# snow_depth_gauge_1D.net
KiCad netlist of a schematic drawn in EAGLE
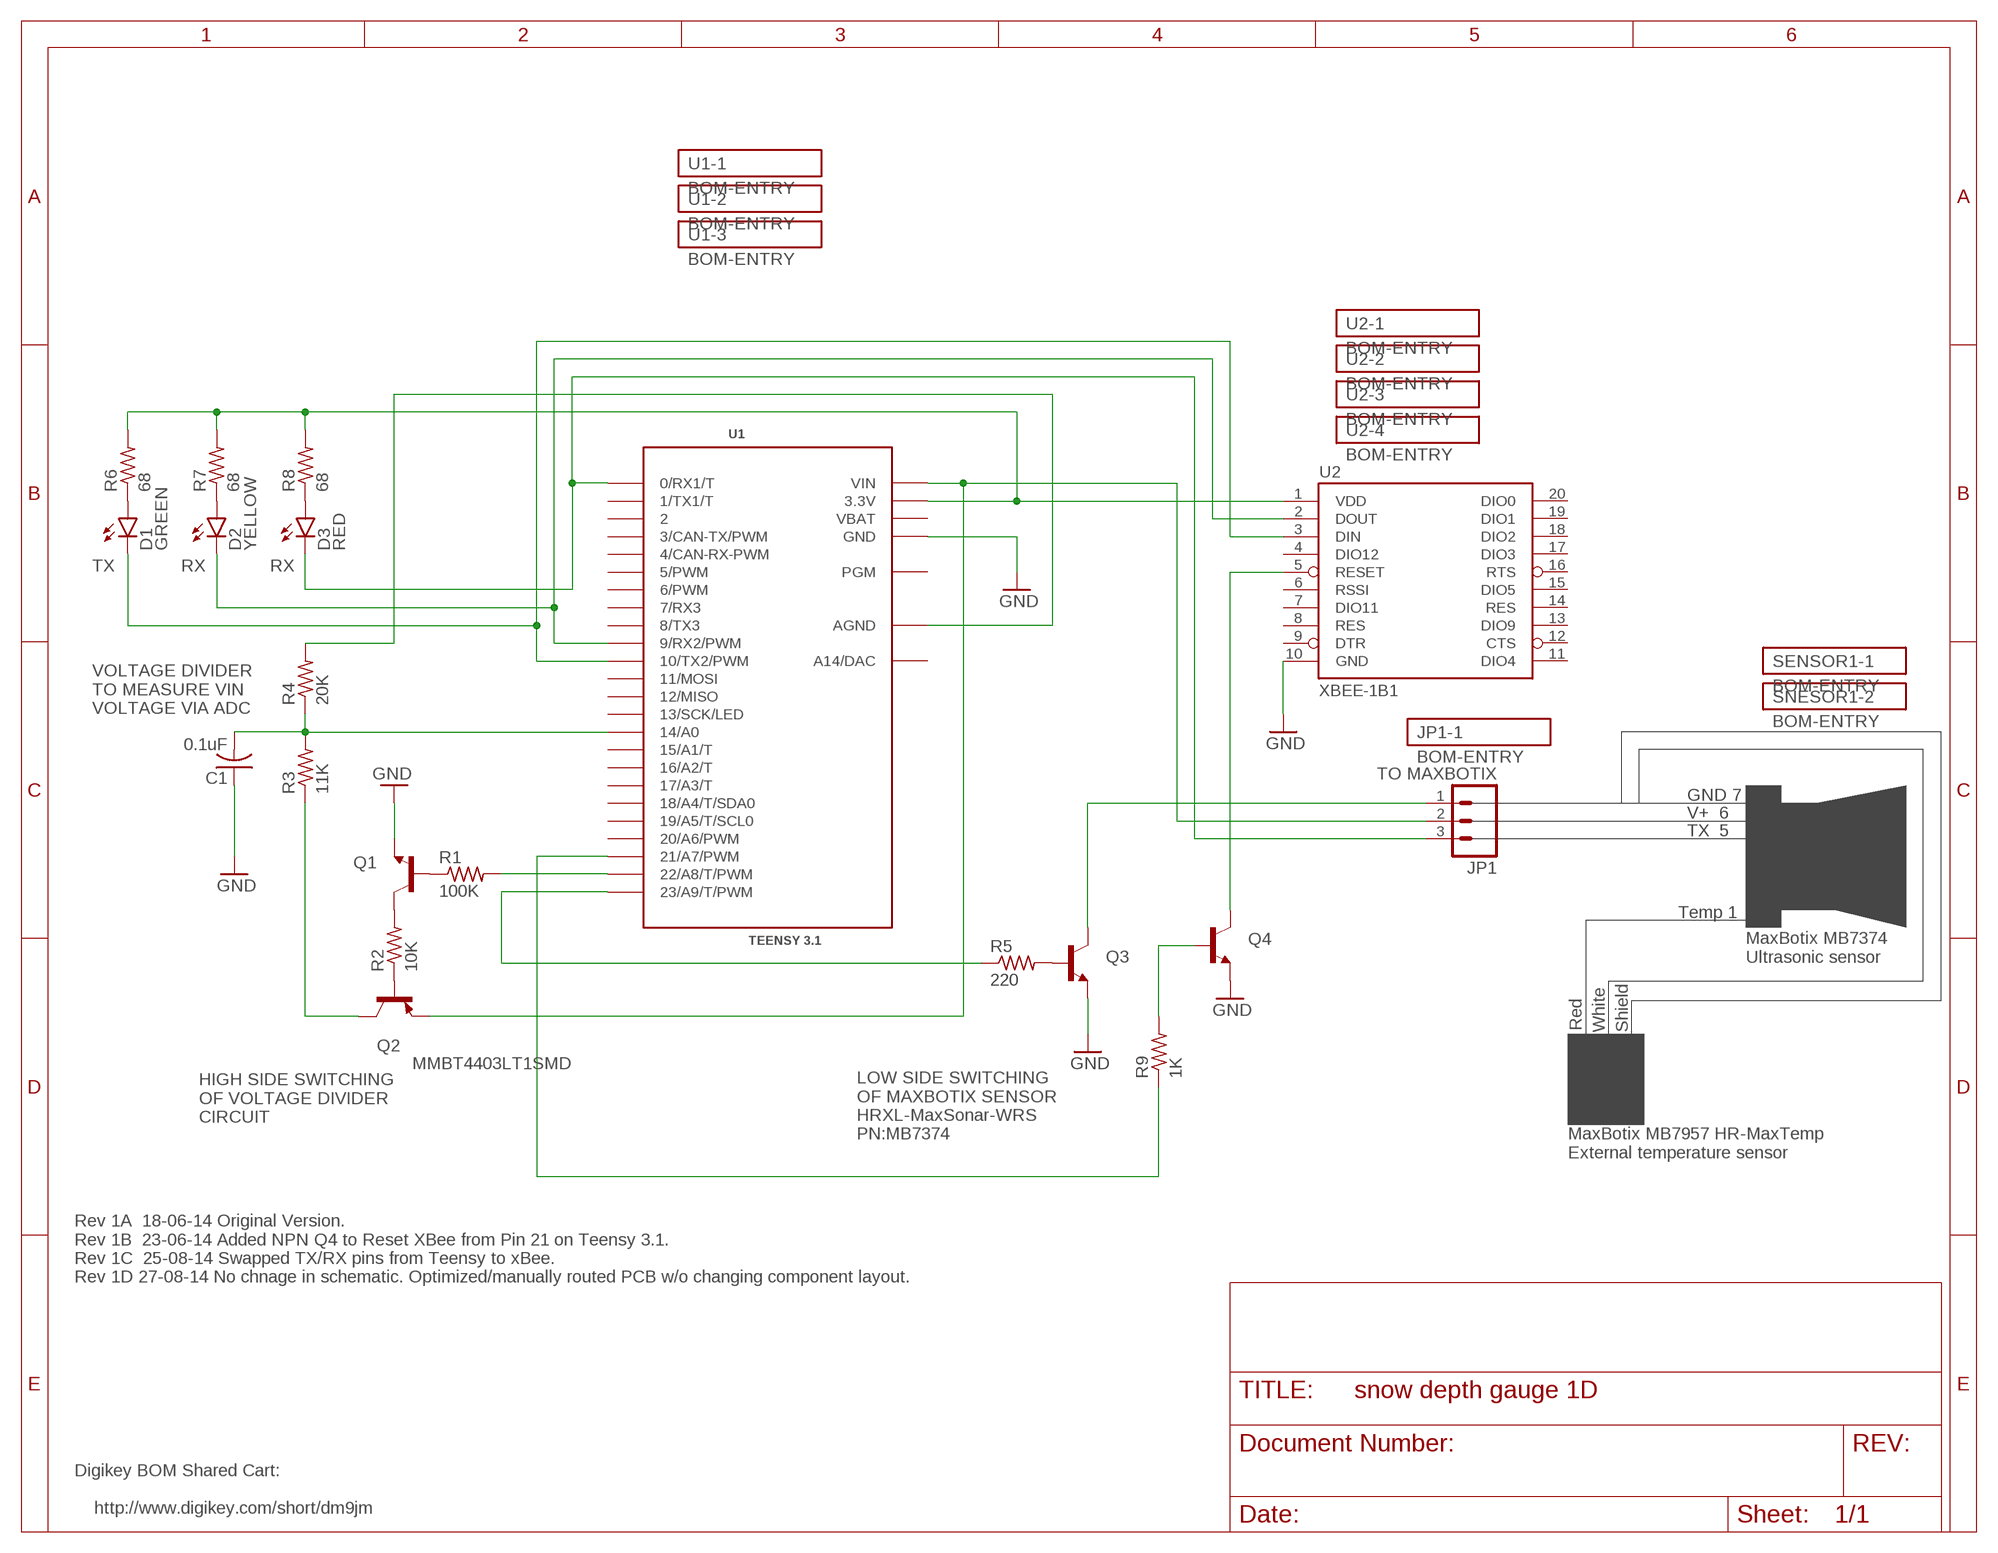
[diagram p0: schematic, sheet 1]

(export (version "E")
  (design (tool "Eeschema 10.0.6"))
  (components
    (comp (ref "C1")
      (value "0.1uF")
      (footprint "eagle-import:C3216")
      (fields (field (name "PARTNO") "C1206C104K4RACTU"))
      (libsource (lib "eagle-import") (part "C-USC3216"))
    )
    (comp (ref "D1")
      (value "GREEN")
      (footprint "eagle-import:LED-0603")
      (fields (field (name "PARTNO") "LNJ337W83RA"))
      (libsource (lib "eagle-import") (part "LED-GREEN0603"))
    )
    (comp (ref "D2")
      (value "YELLOW")
      (footprint "eagle-import:LED-0603")
      (fields (field (name "PARTNO") "LNJ437W84RA"))
      (libsource (lib "eagle-import") (part "LED-YELLOW0603"))
    )
    (comp (ref "D3")
      (value "RED")
      (footprint "eagle-import:LED-0603")
      (fields (field (name "PARTNO") "LNJ237W82RA"))
      (libsource (lib "eagle-import") (part "LED-RED0603"))
    )
    (comp (ref "JP1")
      (value "TO MAXBOTIX")
      (footprint "eagle-import:MOLEX-1X3_LOCK")
      (fields (field (name "PARTNO") "0022292031"))
      (libsource (lib "eagle-import") (part "M03POLAR_LOCK"))
    )
    (comp (ref "Q1")
      (value "MMBT2222ALT1-NPN-SOT23-BEC")
      (footprint "eagle-import:SOT23-BEC")
      (fields (field (name "PARTNO") "MMBT2222A"))
      (libsource (lib "eagle-import") (part "-NPN-SOT23-BECMMBT2222ALT1"))
    )
    (comp (ref "Q2")
      (value "MMBT4403LT1SMD")
      (footprint "eagle-import:SOT23-BEC")
      (fields (field (name "PARTNO") "MMBT4403"))
      (libsource (lib "eagle-import") (part "MMBT4403SMDLT1"))
    )
    (comp (ref "Q3")
      (value "MMBT2222ALT1-NPN-SOT23-BEC")
      (footprint "eagle-import:SOT23-BEC")
      (fields (field (name "PARTNO") "MMBT2222A"))
      (libsource (lib "eagle-import") (part "-NPN-SOT23-BECMMBT2222ALT1"))
    )
    (comp (ref "Q4")
      (value "MMBT2222ALT1-NPN-SOT23-BEC")
      (footprint "eagle-import:SOT23-BEC")
      (fields (field (name "PARTNO") "MMBT2222A"))
      (libsource (lib "eagle-import") (part "-NPN-SOT23-BECMMBT2222ALT1"))
    )
    (comp (ref "R1")
      (value "100K")
      (footprint "eagle-import:R3216")
      (fields (field (name "PARTNO") "KTR18EZPJ104"))
      (libsource (lib "eagle-import") (part "R-US_R3216"))
    )
    (comp (ref "R2")
      (value "10K")
      (footprint "eagle-import:R3216")
      (fields (field (name "PARTNO") "KTR18EZPJ103"))
      (libsource (lib "eagle-import") (part "R-US_R3216"))
    )
    (comp (ref "R3")
      (value "11K")
      (footprint "eagle-import:R3216")
      (fields (field (name "PARTNO") "KTR18EZPF1102"))
      (libsource (lib "eagle-import") (part "R-US_R3216"))
    )
    (comp (ref "R4")
      (value "20K")
      (footprint "eagle-import:R3216")
      (fields (field (name "PARTNO") "KTR18EZPF2002"))
      (libsource (lib "eagle-import") (part "R-US_R3216"))
    )
    (comp (ref "R5")
      (value "220")
      (footprint "eagle-import:R3216")
      (fields (field (name "PARTNO") "KTR18EZPJ221"))
      (libsource (lib "eagle-import") (part "R-US_R3216"))
    )
    (comp (ref "R6")
      (value "68")
      (footprint "eagle-import:R3216")
      (fields (field (name "PARTNO") "KTR18EZPJ680"))
      (libsource (lib "eagle-import") (part "R-US_R3216"))
    )
    (comp (ref "R7")
      (value "68")
      (footprint "eagle-import:R3216")
      (fields (field (name "PARTNO") "KTR18EZPJ680"))
      (libsource (lib "eagle-import") (part "R-US_R3216"))
    )
    (comp (ref "R8")
      (value "68")
      (footprint "eagle-import:R3216")
      (fields (field (name "PARTNO") "KTR18EZPJ680"))
      (libsource (lib "eagle-import") (part "R-US_R3216"))
    )
    (comp (ref "R9")
      (value "1K")
      (footprint "eagle-import:R3216")
      (fields (field (name "PARTNO") "KTR18EZPJ102"))
      (libsource (lib "eagle-import") (part "R-US_R3216"))
    )
    (comp (ref "U1")
      (value "TEENSY 3.1")
      (footprint "eagle-import:TEENSY_3.1_BASIC")
      (fields (field (name "PARTNO") "TEENSY31"))
      (libsource (lib "eagle-import") (part "TEENSY_3.1_BASIC"))
    )
    (comp (ref "U2")
      (value "XBEE-1B1")
      (footprint "eagle-import:XBEE-1")
      (fields (field (name "PARTNO") "XB24-AUI-001"))
      (libsource (lib "eagle-import") (part "XBEE-1B1"))
    )
  )
  (nets
    (net (code "1") (name "/VBAT") (class "Default")
      (node (ref "U1") (pin "VBAT") (pinfunction "VBAT_VBAT") (pintype "power_in"))
    )
    (net (code "2") (name "GND") (class "Default")
      (node (ref "C1") (pin "1") (pinfunction "1_1") (pintype "passive"))
      (node (ref "Q1") (pin "E") (pinfunction "E_E") (pintype "passive"))
      (node (ref "Q3") (pin "E") (pinfunction "E_E") (pintype "passive"))
      (node (ref "Q4") (pin "E") (pinfunction "E_E") (pintype "passive"))
      (node (ref "U1") (pin "GND") (pinfunction "GND_GND") (pintype "power_in"))
      (node (ref "U1") (pin "GND1") (pinfunction "GND_GND1") (pintype "power_in"))
      (node (ref "U2") (pin "10") (pinfunction "GND_10") (pintype "power_in"))
    )
    (net (code "3") (name "Net-(C1-Pad2)") (class "Default")
      (node (ref "C1") (pin "2") (pinfunction "2_2") (pintype "passive"))
      (node (ref "R3") (pin "2") (pinfunction "2_2") (pintype "passive"))
      (node (ref "R4") (pin "1") (pinfunction "1_1") (pintype "passive"))
      (node (ref "U1") (pin "14/A0") (pinfunction "14/A0_14/A0") (pintype "bidirectional"))
    )
    (net (code "4") (name "Net-(D1-PadA)") (class "Default")
      (node (ref "D1") (pin "A") (pinfunction "A_A") (pintype "passive"))
      (node (ref "R6") (pin "1") (pinfunction "1_1") (pintype "passive"))
    )
    (net (code "5") (name "Net-(D2-PadA)") (class "Default")
      (node (ref "D2") (pin "A") (pinfunction "A_A") (pintype "passive"))
      (node (ref "R7") (pin "1") (pinfunction "1_1") (pintype "passive"))
    )
    (net (code "6") (name "Net-(D3-PadA)") (class "Default")
      (node (ref "D3") (pin "A") (pinfunction "A_A") (pintype "passive"))
      (node (ref "R8") (pin "1") (pinfunction "1_1") (pintype "passive"))
    )
    (net (code "7") (name "Net-(JP1-Pad1)") (class "Default")
      (node (ref "JP1") (pin "1") (pinfunction "1_1") (pintype "passive"))
      (node (ref "Q3") (pin "C") (pinfunction "C_C") (pintype "passive"))
    )
    (net (code "8") (name "Net-(JP1-Pad2)") (class "Default")
      (node (ref "JP1") (pin "2") (pinfunction "2_2") (pintype "passive"))
      (node (ref "Q2") (pin "E") (pinfunction "E_E") (pintype "passive"))
      (node (ref "U1") (pin "VIN") (pinfunction "VIN_VIN") (pintype "power_in"))
    )
    (net (code "9") (name "Net-(Q1-PadB)") (class "Default")
      (node (ref "Q1") (pin "B") (pinfunction "B_B") (pintype "passive"))
      (node (ref "R1") (pin "1") (pinfunction "1_1") (pintype "passive"))
    )
    (net (code "10") (name "Net-(Q1-PadC)") (class "Default")
      (node (ref "Q1") (pin "C") (pinfunction "C_C") (pintype "passive"))
      (node (ref "R2") (pin "2") (pinfunction "2_2") (pintype "passive"))
    )
    (net (code "11") (name "Net-(Q2-PadB)") (class "Default")
      (node (ref "Q2") (pin "B") (pinfunction "B_B") (pintype "passive"))
      (node (ref "R2") (pin "1") (pinfunction "1_1") (pintype "passive"))
    )
    (net (code "12") (name "Net-(Q2-PadC)") (class "Default")
      (node (ref "Q2") (pin "C") (pinfunction "C_C") (pintype "passive"))
      (node (ref "R3") (pin "1") (pinfunction "1_1") (pintype "passive"))
    )
    (net (code "13") (name "Net-(Q3-PadB)") (class "Default")
      (node (ref "Q3") (pin "B") (pinfunction "B_B") (pintype "passive"))
      (node (ref "R5") (pin "2") (pinfunction "2_2") (pintype "passive"))
    )
    (net (code "14") (name "Net-(Q4-PadB)") (class "Default")
      (node (ref "Q4") (pin "B") (pinfunction "B_B") (pintype "passive"))
      (node (ref "R9") (pin "2") (pinfunction "2_2") (pintype "passive"))
    )
    (net (code "15") (name "Net-(R4-Pad2)") (class "Default")
      (node (ref "R4") (pin "2") (pinfunction "2_2") (pintype "passive"))
      (node (ref "U1") (pin "AGND") (pinfunction "AGND_AGND") (pintype "power_in"))
    )
    (net (code "16") (name "Net-(U1-0{slash}RX1{slash}T)") (class "Default")
      (node (ref "D3") (pin "C") (pinfunction "C_C") (pintype "passive"))
      (node (ref "JP1") (pin "3") (pinfunction "3_3") (pintype "passive"))
      (node (ref "U1") (pin "0") (pinfunction "0/RX1/T_0") (pintype "bidirectional"))
    )
    (net (code "17") (name "Net-(U1-9{slash}RX2{slash}PWM)") (class "Default")
      (node (ref "D2") (pin "C") (pinfunction "C_C") (pintype "passive"))
      (node (ref "U1") (pin "9") (pinfunction "9/RX2/PWM_9") (pintype "bidirectional"))
      (node (ref "U2") (pin "2") (pinfunction "DOUT_2") (pintype "output"))
    )
    (net (code "18") (name "Net-(U1-10{slash}TX2{slash}PWM)") (class "Default")
      (node (ref "D1") (pin "C") (pinfunction "C_C") (pintype "passive"))
      (node (ref "U1") (pin "10") (pinfunction "10/TX2/PWM_10") (pintype "bidirectional"))
      (node (ref "U2") (pin "3") (pinfunction "DIN_3") (pintype "input"))
    )
    (net (code "19") (name "Net-(U1-21{slash}A7{slash}PWM)") (class "Default")
      (node (ref "R9") (pin "1") (pinfunction "1_1") (pintype "passive"))
      (node (ref "U1") (pin "21/A7") (pinfunction "21/A7/PWM_21/A7") (pintype "bidirectional"))
    )
    (net (code "20") (name "Net-(U1-22{slash}A8{slash}T{slash}PWM)") (class "Default")
      (node (ref "R1") (pin "2") (pinfunction "2_2") (pintype "passive"))
      (node (ref "U1") (pin "22/A8") (pinfunction "22/A8/T/PWM_22/A8") (pintype "bidirectional"))
    )
    (net (code "21") (name "Net-(U1-23{slash}A9{slash}T{slash}PWM)") (class "Default")
      (node (ref "R5") (pin "1") (pinfunction "1_1") (pintype "passive"))
      (node (ref "U1") (pin "23/A9") (pinfunction "23/A9/T/PWM_23/A9") (pintype "bidirectional"))
    )
    (net (code "22") (name "Net-(U2-RESET)") (class "Default")
      (node (ref "Q4") (pin "C") (pinfunction "C_C") (pintype "passive"))
      (node (ref "U2") (pin "5") (pinfunction "RESET_5") (pintype "input"))
    )
    (net (code "23") (name "Net-(U2-VDD)") (class "Default")
      (node (ref "R6") (pin "2") (pinfunction "2_2") (pintype "passive"))
      (node (ref "R7") (pin "2") (pinfunction "2_2") (pintype "passive"))
      (node (ref "R8") (pin "2") (pinfunction "2_2") (pintype "passive"))
      (node (ref "U1") (pin "3.3V") (pinfunction "3.3V_3.3V") (pintype "power_in"))
      (node (ref "U1") (pin "3.3V1") (pinfunction "3.3V_3.3V1") (pintype "power_in"))
      (node (ref "U2") (pin "1") (pinfunction "VDD_1") (pintype "power_in"))
    )
    (net (code "24") (name "unconnected-(U1-1{slash}TX1{slash}T-Pad1)") (class "Default")
      (node (ref "U1") (pin "1") (pinfunction "1/TX1/T_1") (pintype "bidirectional"))
    )
    (net (code "25") (name "unconnected-(U1-3{slash}CAN-TX{slash}PWM-Pad3)") (class "Default")
      (node (ref "U1") (pin "3") (pinfunction "3/CAN-TX/PWM_3") (pintype "bidirectional"))
    )
    (net (code "26") (name "unconnected-(U1-4{slash}CAN-RX-PWM-Pad4)") (class "Default")
      (node (ref "U1") (pin "4") (pinfunction "4/CAN-RX-PWM_4") (pintype "bidirectional"))
    )
    (net (code "27") (name "unconnected-(U1-5{slash}PWM-Pad5)") (class "Default")
      (node (ref "U1") (pin "5") (pinfunction "5/PWM_5") (pintype "bidirectional"))
    )
    (net (code "28") (name "unconnected-(U1-6{slash}PWM-Pad6)") (class "Default")
      (node (ref "U1") (pin "6") (pinfunction "6/PWM_6") (pintype "bidirectional"))
    )
    (net (code "29") (name "unconnected-(U1-7{slash}RX3-Pad7)") (class "Default")
      (node (ref "U1") (pin "7") (pinfunction "7/RX3_7") (pintype "bidirectional"))
    )
    (net (code "30") (name "unconnected-(U1-8{slash}TX3-Pad8)") (class "Default")
      (node (ref "U1") (pin "8") (pinfunction "8/TX3_8") (pintype "bidirectional"))
    )
    (net (code "31") (name "unconnected-(U1-11{slash}MOSI-Pad11)") (class "Default")
      (node (ref "U1") (pin "11") (pinfunction "11/MOSI_11") (pintype "bidirectional"))
    )
    (net (code "32") (name "unconnected-(U1-12{slash}MISO-Pad12)") (class "Default")
      (node (ref "U1") (pin "12") (pinfunction "12/MISO_12") (pintype "bidirectional"))
    )
    (net (code "33") (name "unconnected-(U1-13{slash}SCK{slash}LED-Pad13)") (class "Default")
      (node (ref "U1") (pin "13") (pinfunction "13/SCK/LED_13") (pintype "bidirectional"))
    )
    (net (code "34") (name "unconnected-(U1-15{slash}A1{slash}T-Pad15{slash}A1)") (class "Default")
      (node (ref "U1") (pin "15/A1") (pinfunction "15/A1/T_15/A1") (pintype "bidirectional"))
    )
    (net (code "35") (name "unconnected-(U1-16{slash}A2{slash}T-Pad16{slash}A2)") (class "Default")
      (node (ref "U1") (pin "16/A2") (pinfunction "16/A2/T_16/A2") (pintype "bidirectional"))
    )
    (net (code "36") (name "unconnected-(U1-17{slash}A3{slash}T-Pad17{slash}A3)") (class "Default")
      (node (ref "U1") (pin "17/A3") (pinfunction "17/A3/T_17/A3") (pintype "bidirectional"))
    )
    (net (code "37") (name "unconnected-(U1-18{slash}A4{slash}T{slash}SDA0-Pad18{slash}A4)") (class "Default")
      (node (ref "U1") (pin "18/A4") (pinfunction "18/A4/T/SDA0_18/A4") (pintype "bidirectional"))
    )
    (net (code "38") (name "unconnected-(U1-19{slash}A5{slash}T{slash}SCL0-Pad19{slash}A5)") (class "Default")
      (node (ref "U1") (pin "19/A5") (pinfunction "19/A5/T/SCL0_19/A5") (pintype "bidirectional"))
    )
    (net (code "39") (name "unconnected-(U1-20{slash}A6{slash}PWM-Pad20{slash}A6)") (class "Default")
      (node (ref "U1") (pin "20/A6") (pinfunction "20/A6/PWM_20/A6") (pintype "bidirectional"))
    )
    (net (code "40") (name "unconnected-(U1-A14{slash}DAC-PadA14)") (class "Default")
      (node (ref "U1") (pin "A14") (pinfunction "A14/DAC_A14") (pintype "bidirectional"))
    )
    (net (code "41") (name "unconnected-(U1-Pad2)") (class "Default")
      (node (ref "U1") (pin "2") (pinfunction "2_2") (pintype "bidirectional"))
    )
    (net (code "42") (name "unconnected-(U1-PadPGM)") (class "Default")
      (node (ref "U1") (pin "PGM") (pinfunction "PGM_PGM") (pintype "bidirectional"))
    )
    (net (code "43") (name "unconnected-(U2-CTS-Pad12)") (class "Default")
      (node (ref "U2") (pin "12") (pinfunction "CTS_12") (pintype "output"))
    )
    (net (code "44") (name "unconnected-(U2-DIO0-Pad20)") (class "Default")
      (node (ref "U2") (pin "20") (pinfunction "DIO0_20") (pintype "bidirectional"))
    )
    (net (code "45") (name "unconnected-(U2-DIO1-Pad19)") (class "Default")
      (node (ref "U2") (pin "19") (pinfunction "DIO1_19") (pintype "bidirectional"))
    )
    (net (code "46") (name "unconnected-(U2-DIO2-Pad18)") (class "Default")
      (node (ref "U2") (pin "18") (pinfunction "DIO2_18") (pintype "bidirectional"))
    )
    (net (code "47") (name "unconnected-(U2-DIO3-Pad17)") (class "Default")
      (node (ref "U2") (pin "17") (pinfunction "DIO3_17") (pintype "bidirectional"))
    )
    (net (code "48") (name "unconnected-(U2-DIO4-Pad11)") (class "Default")
      (node (ref "U2") (pin "11") (pinfunction "DIO4_11") (pintype "bidirectional"))
    )
    (net (code "49") (name "unconnected-(U2-DIO5-Pad15)") (class "Default")
      (node (ref "U2") (pin "15") (pinfunction "DIO5_15") (pintype "bidirectional"))
    )
    (net (code "50") (name "unconnected-(U2-DIO9-Pad13)") (class "Default")
      (node (ref "U2") (pin "13") (pinfunction "DIO9_13") (pintype "bidirectional"))
    )
    (net (code "51") (name "unconnected-(U2-DIO11-Pad7)") (class "Default")
      (node (ref "U2") (pin "7") (pinfunction "DIO11_7") (pintype "bidirectional"))
    )
    (net (code "52") (name "unconnected-(U2-DIO12-Pad4)") (class "Default")
      (node (ref "U2") (pin "4") (pinfunction "DIO12_4") (pintype "bidirectional"))
    )
    (net (code "53") (name "unconnected-(U2-DTR-Pad9)") (class "Default")
      (node (ref "U2") (pin "9") (pinfunction "DTR_9") (pintype "bidirectional"))
    )
    (net (code "54") (name "unconnected-(U2-RES-Pad8)") (class "Default")
      (node (ref "U2") (pin "8") (pinfunction "RES_8") (pintype "bidirectional"))
    )
    (net (code "55") (name "unconnected-(U2-RES-Pad14)") (class "Default")
      (node (ref "U2") (pin "14") (pinfunction "RES_14") (pintype "bidirectional"))
    )
    (net (code "56") (name "unconnected-(U2-RSSI-Pad6)") (class "Default")
      (node (ref "U2") (pin "6") (pinfunction "RSSI_6") (pintype "bidirectional"))
    )
    (net (code "57") (name "unconnected-(U2-RTS-Pad16)") (class "Default")
      (node (ref "U2") (pin "16") (pinfunction "RTS_16") (pintype "input"))
    )
  )
)
